# M26_T_V1_0b.net
KiCad netlist of a schematic drawn in Altium Designer
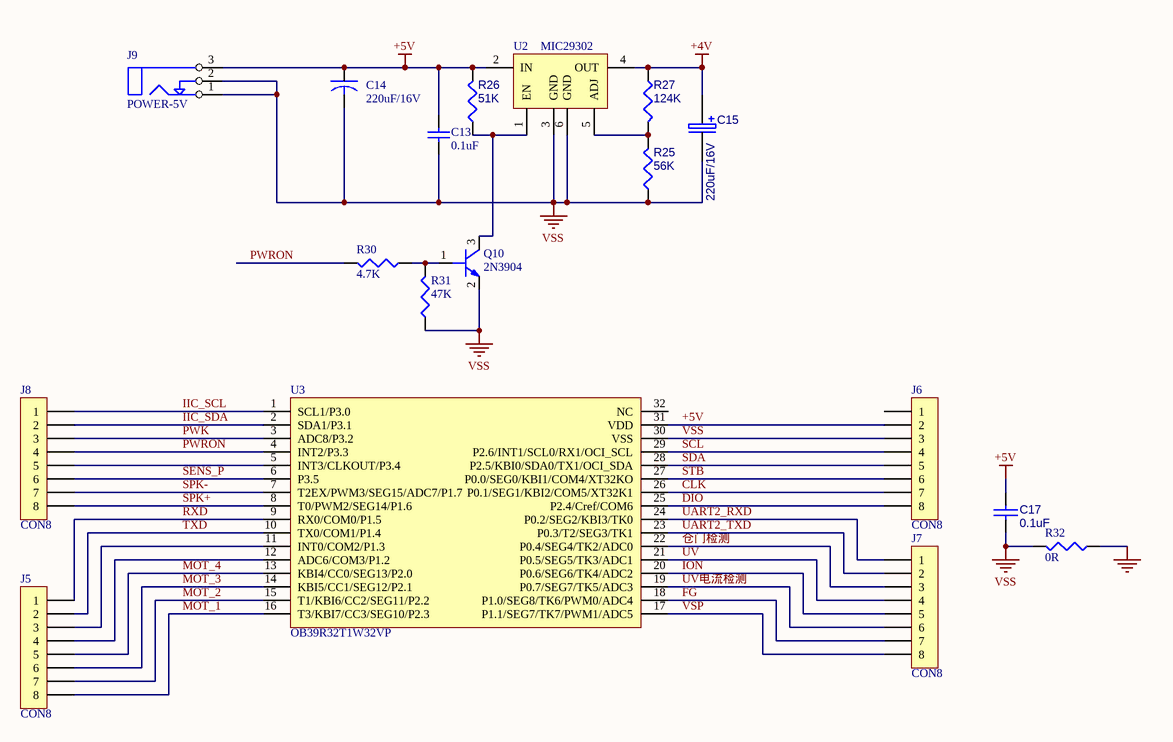
[diagram p0: M26_T_V1.0b.SchDoc]

(export (version "E")
  (design (tool "Eeschema 10.0.6"))
  (components
    (comp (ref "C13")
      (value "0.1uF")
      (footprint "0805_C")
      (description "Capacitor")
      (fields (field (name "PUBLISHER") "Altium Limited"))
      (libsource (lib "EP_MCB_V3.00") (part "Cap Semi"))
    )
    (comp (ref "C14")
      (value "220uF/16V")
      (footprint "C_TAN_D")
      (libsource (lib "EM_SENSOR_V3.01") (part "C"))
    )
    (comp (ref "C15")
      (value "220uF/16V")
      (footprint "C_TAN_D")
      (description "E-CAP")
      (libsource (lib "*") (part "ECAP"))
    )
    (comp (ref "C17")
      (value "0.1uF")
      (footprint "0805_C")
      (description "CAP")
      (libsource (lib "*") (part "CAP"))
    )
    (comp (ref "J5") (value "CON8") (footprint "SIP-8") (libsource (lib "") (part "CON8_1")))
    (comp (ref "J6") (value "CON8") (footprint "SIP-8") (libsource (lib "MySchlib") (part "CON8")))
    (comp (ref "J7") (value "CON8") (footprint "SIP-8") (libsource (lib "MySchlib") (part "CON8")))
    (comp (ref "J8") (value "CON8") (footprint "SIP-8") (libsource (lib "") (part "CON8_1")))
    (comp (ref "J9") (value "POWER-5V") (footprint "DC_5") (libsource (lib "MySchlib") (part "POWER-5V")))
    (comp (ref "Q10") (value "2N3904") (footprint "SOT23") (libsource (lib "MySchlib") (part "NPN")))
    (comp (ref "R25")
      (value "56K")
      (footprint "0603_R")
      (description "RESISTOR")
      (libsource (lib "*") (part "R0.25W"))
    )
    (comp (ref "R26")
      (value "51K")
      (footprint "0603_R")
      (description "RESISTOR")
      (libsource (lib "*") (part "R0.25W"))
    )
    (comp (ref "R27")
      (value "124K")
      (footprint "0603_R")
      (description "RESISTOR")
      (libsource (lib "*") (part "R0.25W"))
    )
    (comp (ref "R30") (value "4.7K") (footprint "0603_R") (libsource (lib "") (part "RES1_1")))
    (comp (ref "R31") (value "47K") (footprint "0603_R") (libsource (lib "") (part "RES1_1")))
    (comp (ref "R32") (value "0R") (footprint "0603_R") (libsource (lib "MySchlib") (part "RES1")))
    (comp (ref "U2") (value "MIC29302") (footprint "TO-263-5") (libsource (lib "MySchlib") (part "MIC29302")))
    (comp (ref "U3")
      (value "OB39R32T1W32VP")
      (footprint "LQFP32")
      (libsource (lib "MySchlib") (part "OB39R32T1W32VP"))
    )
  )
  (nets
    (net (code "1") (name "+4V") (class "Default")
      (node (ref "C15") (pin "1") (pinfunction "+_1") (pintype "passive"))
      (node (ref "R27") (pin "2") (pinfunction "2_2") (pintype "passive"))
      (node (ref "U2") (pin "4") (pinfunction "OUT_4") (pintype "passive"))
    )
    (net (code "2") (name "+5V") (class "Default")
      (node (ref "C13") (pin "2") (pinfunction "2_2") (pintype "passive"))
      (node (ref "C14") (pin "1") (pinfunction "1_1") (pintype "passive"))
      (node (ref "C17") (pin "1") (pinfunction "1_1") (pintype "passive"))
      (node (ref "J6") (pin "2") (pinfunction "2_2") (pintype "passive"))
      (node (ref "J9") (pin "3") (pinfunction "3_3") (pintype "passive"))
      (node (ref "R26") (pin "1") (pinfunction "1_1") (pintype "passive"))
      (node (ref "U2") (pin "2") (pinfunction "IN_2") (pintype "passive"))
      (node (ref "U3") (pin "31") (pinfunction "VDD_31") (pintype "passive"))
    )
    (net (code "3") (name "/CLK") (class "Default")
      (node (ref "J6") (pin "7") (pinfunction "7_7") (pintype "passive"))
      (node (ref "U3") (pin "26") (pinfunction "P0.1/SEG1/KBI2/COM5/XT32K1_26") (pintype "passive"))
    )
    (net (code "4") (name "/DIO") (class "Default")
      (node (ref "J6") (pin "8") (pinfunction "8_8") (pintype "passive"))
      (node (ref "U3") (pin "25") (pinfunction "P2.4/Cref/COM6_25") (pintype "passive"))
    )
    (net (code "5") (name "/FG") (class "Default")
      (node (ref "J7") (pin "7") (pinfunction "7_7") (pintype "passive"))
      (node (ref "U3") (pin "18") (pinfunction "P1.0/SEG8/TK6/PWM0/ADC4_18") (pintype "passive"))
    )
    (net (code "6") (name "/IIC_SCL") (class "Default")
      (node (ref "J8") (pin "1") (pinfunction "1_1") (pintype "passive"))
      (node (ref "U3") (pin "1") (pinfunction "SCL1/P3.0_1") (pintype "passive"))
    )
    (net (code "7") (name "/IIC_SDA") (class "Default")
      (node (ref "J8") (pin "2") (pinfunction "2_2") (pintype "passive"))
      (node (ref "U3") (pin "2") (pinfunction "SDA1/P3.1_2") (pintype "passive"))
    )
    (net (code "8") (name "/ION") (class "Default")
      (node (ref "J7") (pin "5") (pinfunction "5_5") (pintype "passive"))
      (node (ref "U3") (pin "20") (pinfunction "P0.6/SEG6/TK4/ADC2_20") (pintype "passive"))
    )
    (net (code "9") (name "/MOT_1") (class "Default")
      (node (ref "J5") (pin "8") (pinfunction "8_8") (pintype "passive"))
      (node (ref "U3") (pin "16") (pinfunction "T3/KBI7/CC3/SEG10/P2.3_16") (pintype "passive"))
    )
    (net (code "10") (name "/MOT_2") (class "Default")
      (node (ref "J5") (pin "7") (pinfunction "7_7") (pintype "passive"))
      (node (ref "U3") (pin "15") (pinfunction "T1/KBI6/CC2/SEG11/P2.2_15") (pintype "passive"))
    )
    (net (code "11") (name "/MOT_3") (class "Default")
      (node (ref "J5") (pin "6") (pinfunction "6_6") (pintype "passive"))
      (node (ref "U3") (pin "14") (pinfunction "KBI5/CC1/SEG12/P2.1_14") (pintype "passive"))
    )
    (net (code "12") (name "/MOT_4") (class "Default")
      (node (ref "J5") (pin "5") (pinfunction "5_5") (pintype "passive"))
      (node (ref "U3") (pin "13") (pinfunction "KBI4/CC0/SEG13/P2.0_13") (pintype "passive"))
    )
    (net (code "13") (name "/PWK") (class "Default")
      (node (ref "J8") (pin "3") (pinfunction "3_3") (pintype "passive"))
      (node (ref "U3") (pin "3") (pinfunction "ADC8/P3.2_3") (pintype "passive"))
    )
    (net (code "14") (name "/PWRON") (class "Default")
      (node (ref "J8") (pin "4") (pinfunction "4_4") (pintype "passive"))
      (node (ref "R30") (pin "1") (pinfunction "1_1") (pintype "passive"))
      (node (ref "U3") (pin "4") (pinfunction "INT2/P3.3_4") (pintype "passive"))
    )
    (net (code "15") (name "/RXD") (class "Default")
      (node (ref "J5") (pin "1") (pinfunction "1_1") (pintype "passive"))
      (node (ref "U3") (pin "9") (pinfunction "RX0/COM0/P1.5_9") (pintype "passive"))
    )
    (net (code "16") (name "/SCL") (class "Default")
      (node (ref "J6") (pin "4") (pinfunction "4_4") (pintype "passive"))
      (node (ref "U3") (pin "29") (pinfunction "P2.6/INT1/SCL0/RX1/OCI_SCL_29") (pintype "passive"))
    )
    (net (code "17") (name "/SDA") (class "Default")
      (node (ref "J6") (pin "5") (pinfunction "5_5") (pintype "passive"))
      (node (ref "U3") (pin "28") (pinfunction "P2.5/KBI0/SDA0/TX1/OCI_SDA_28") (pintype "passive"))
    )
    (net (code "18") (name "/SENS_P") (class "Default")
      (node (ref "J8") (pin "6") (pinfunction "6_6") (pintype "passive"))
      (node (ref "U3") (pin "6") (pinfunction "P3.5_6") (pintype "passive"))
    )
    (net (code "19") (name "/SPK+") (class "Default")
      (node (ref "J8") (pin "8") (pinfunction "8_8") (pintype "passive"))
      (node (ref "U3") (pin "8") (pinfunction "T0/PWM2/SEG14/P1.6_8") (pintype "passive"))
    )
    (net (code "20") (name "/SPK-") (class "Default")
      (node (ref "J8") (pin "7") (pinfunction "7_7") (pintype "passive"))
      (node (ref "U3") (pin "7") (pinfunction "T2EX/PWM3/SEG15/ADC7/P1.7_7") (pintype "passive"))
    )
    (net (code "21") (name "/STB") (class "Default")
      (node (ref "J6") (pin "6") (pinfunction "6_6") (pintype "passive"))
      (node (ref "U3") (pin "27") (pinfunction "P0.0/SEG0/KBI1/COM4/XT32KO_27") (pintype "passive"))
    )
    (net (code "22") (name "/TXD") (class "Default")
      (node (ref "J5") (pin "2") (pinfunction "2_2") (pintype "passive"))
      (node (ref "U3") (pin "10") (pinfunction "TX0/COM1/P1.4_10") (pintype "passive"))
    )
    (net (code "23") (name "/UART2_RXD") (class "Default")
      (node (ref "J7") (pin "1") (pinfunction "1_1") (pintype "passive"))
      (node (ref "U3") (pin "24") (pinfunction "P0.2/SEG2/KBI3/TK0_24") (pintype "passive"))
    )
    (net (code "24") (name "/UART2_TXD") (class "Default")
      (node (ref "J7") (pin "2") (pinfunction "2_2") (pintype "passive"))
      (node (ref "U3") (pin "23") (pinfunction "P0.3/T2/SEG3/TK1_23") (pintype "passive"))
    )
    (net (code "25") (name "/UV") (class "Default")
      (node (ref "J7") (pin "4") (pinfunction "4_4") (pintype "passive"))
      (node (ref "U3") (pin "21") (pinfunction "P0.5/SEG5/TK3/ADC1_21") (pintype "passive"))
    )
    (net (code "26") (name "/UV电流检测") (class "Default")
      (node (ref "J7") (pin "6") (pinfunction "6_6") (pintype "passive"))
      (node (ref "U3") (pin "19") (pinfunction "P0.7/SEG7/TK5/ADC3_19") (pintype "passive"))
    )
    (net (code "27") (name "/VSP") (class "Default")
      (node (ref "J7") (pin "8") (pinfunction "8_8") (pintype "passive"))
      (node (ref "U3") (pin "17") (pinfunction "P1.1/SEG7/TK7/PWM1/ADC5_17") (pintype "passive"))
    )
    (net (code "28") (name "/仓门检测") (class "Default")
      (node (ref "J7") (pin "3") (pinfunction "3_3") (pintype "passive"))
      (node (ref "U3") (pin "22") (pinfunction "P0.4/SEG4/TK2/ADC0_22") (pintype "passive"))
    )
    (net (code "29") (name "GND") (class "Default")
      (node (ref "R32") (pin "2") (pinfunction "2_2") (pintype "passive"))
    )
    (net (code "30") (name "Net-(Q10-BASE)") (class "Default")
      (node (ref "Q10") (pin "1") (pinfunction "BASE_1") (pintype "passive"))
      (node (ref "R30") (pin "2") (pinfunction "2_2") (pintype "passive"))
      (node (ref "R31") (pin "1") (pinfunction "1_1") (pintype "passive"))
    )
    (net (code "31") (name "Net-(Q10-COLLECTOR)") (class "Default")
      (node (ref "Q10") (pin "3") (pinfunction "COLLECTOR_3") (pintype "passive"))
      (node (ref "R26") (pin "2") (pinfunction "2_2") (pintype "passive"))
      (node (ref "U2") (pin "1") (pinfunction "EN_1") (pintype "passive"))
    )
    (net (code "32") (name "Net-(U2-ADJ)") (class "Default")
      (node (ref "R25") (pin "1") (pinfunction "1_1") (pintype "passive"))
      (node (ref "R27") (pin "1") (pinfunction "1_1") (pintype "passive"))
      (node (ref "U2") (pin "5") (pinfunction "ADJ_5") (pintype "passive"))
    )
    (net (code "33") (name "Net-(U3-ADC6{slash}COM3{slash}P1.2)") (class "Default")
      (node (ref "J5") (pin "4") (pinfunction "4_4") (pintype "passive"))
      (node (ref "U3") (pin "12") (pinfunction "ADC6/COM3/P1.2_12") (pintype "passive"))
    )
    (net (code "34") (name "Net-(U3-INT0{slash}COM2{slash}P1.3)") (class "Default")
      (node (ref "J5") (pin "3") (pinfunction "3_3") (pintype "passive"))
      (node (ref "U3") (pin "11") (pinfunction "INT0/COM2/P1.3_11") (pintype "passive"))
    )
    (net (code "35") (name "Net-(U3-INT3{slash}CLKOUT{slash}P3.4)") (class "Default")
      (node (ref "J8") (pin "5") (pinfunction "5_5") (pintype "passive"))
      (node (ref "U3") (pin "5") (pinfunction "INT3/CLKOUT/P3.4_5") (pintype "passive"))
    )
    (net (code "36") (name "VSS") (class "Default")
      (node (ref "C13") (pin "1") (pinfunction "1_1") (pintype "passive"))
      (node (ref "C14") (pin "2") (pinfunction "2_2") (pintype "passive"))
      (node (ref "C15") (pin "2") (pinfunction "-_2") (pintype "passive"))
      (node (ref "C17") (pin "2") (pinfunction "2_2") (pintype "passive"))
      (node (ref "J6") (pin "3") (pinfunction "3_3") (pintype "passive"))
      (node (ref "J9") (pin "1") (pinfunction "1_1") (pintype "passive"))
      (node (ref "J9") (pin "2") (pinfunction "2_2") (pintype "passive"))
      (node (ref "Q10") (pin "2") (pinfunction "EMITTER_2") (pintype "passive"))
      (node (ref "R25") (pin "2") (pinfunction "2_2") (pintype "passive"))
      (node (ref "R31") (pin "2") (pinfunction "2_2") (pintype "passive"))
      (node (ref "R32") (pin "1") (pinfunction "1_1") (pintype "passive"))
      (node (ref "U2") (pin "3") (pinfunction "GND_3") (pintype "passive"))
      (node (ref "U2") (pin "6") (pinfunction "GND_6") (pintype "passive"))
      (node (ref "U3") (pin "30") (pinfunction "VSS_30") (pintype "passive"))
    )
    (net (code "37") (name "unconnected-(J6-Pad1)") (class "Default")
      (node (ref "J6") (pin "1") (pinfunction "1_1") (pintype "passive"))
    )
    (net (code "38") (name "unconnected-(U3-NC-Pad32)") (class "Default")
      (node (ref "U3") (pin "32") (pinfunction "NC_32") (pintype "passive"))
    )
  )
)
